# 780-00055_rev2_Pg1_SCH_NRES_Temp_Meas_8-.net
KiCad netlist of a schematic drawn in Altium Designer
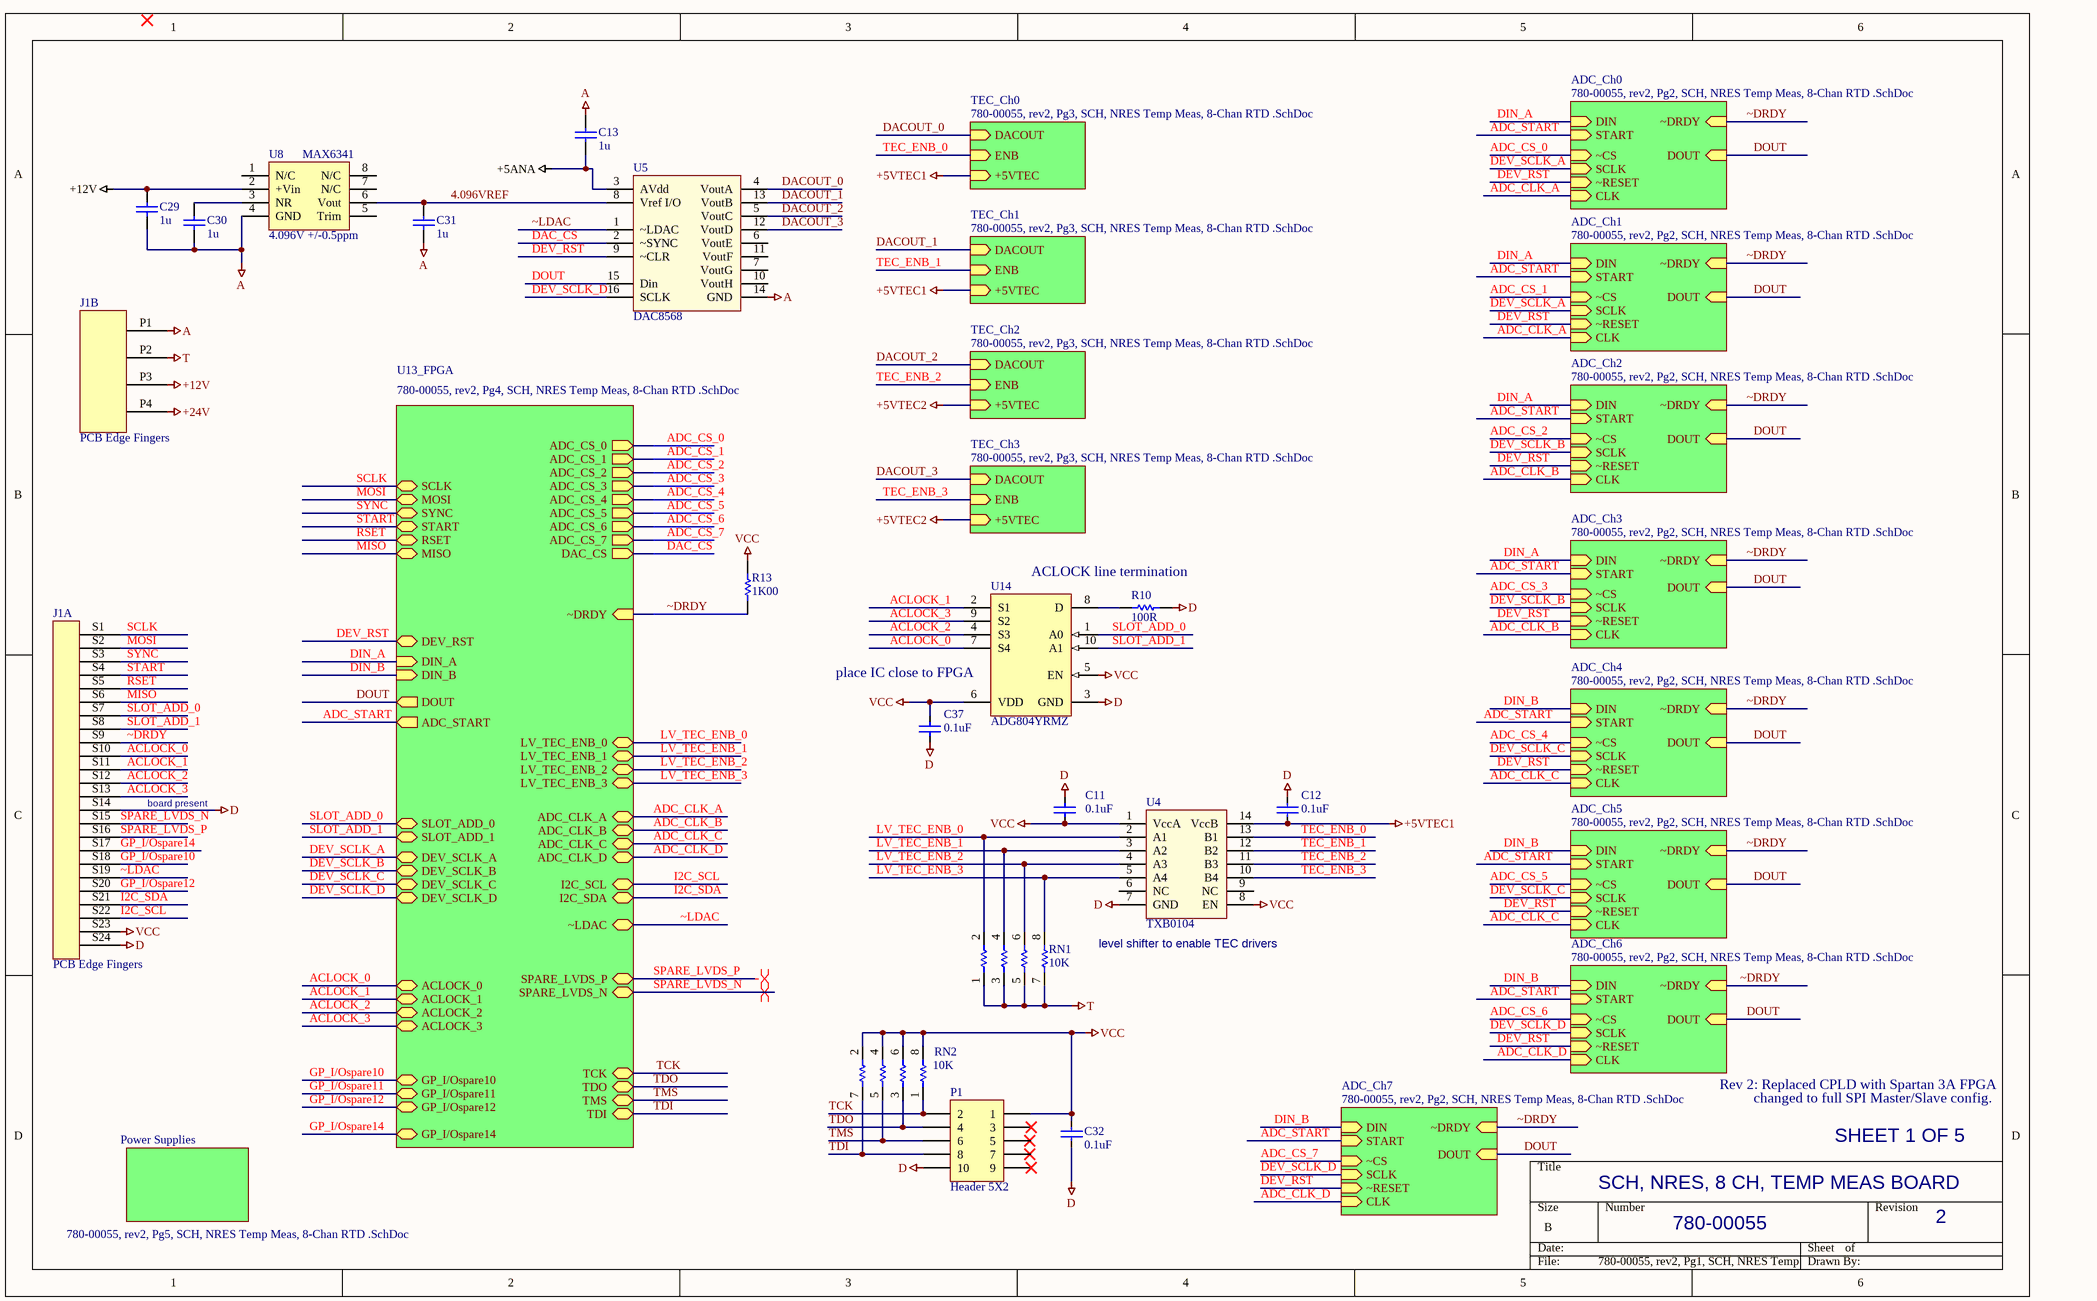
[diagram p0: 780-00055, rev2, Pg1, SCH, NRES Temp Meas, 8-Chan RTD .SchDoc]

(export (version "E")
  (design (tool "Eeschema 10.0.6"))
  (components
    (comp (ref "C11")
      (value "0.1uF")
      (footprint "SMD_0805")
      (description "Capacitor")
      (fields (field (name "Comment") "Cap SMD"))
      (libsource (lib "Richs Schematic Components") (part "Cap SMD"))
    )
    (comp (ref "C12")
      (value "0.1uF")
      (footprint "SMD_0805")
      (description "Capacitor")
      (fields (field (name "Comment") "Cap SMD"))
      (libsource (lib "Richs Schematic Components") (part "Cap SMD"))
    )
    (comp (ref "C13")
      (value "1u")
      (footprint "SMD_0805")
      (description "Capacitor")
      (fields (field (name "MANUFACTURER") "Taiyo Yuden"))
      (libsource (lib "Miscellaneous Devices") (part "Cap"))
    )
    (comp (ref "C29")
      (value "1u")
      (footprint "SMD_0805")
      (description "Capacitor")
      (fields (field (name "MANUFACTURER") "Taiyo Yuden"))
      (libsource (lib "Miscellaneous Devices") (part "Cap"))
    )
    (comp (ref "C30")
      (value "1u")
      (footprint "SMD_0805")
      (description "Capacitor")
      (fields (field (name "MANUFACTURER") "Taiyo Yuden"))
      (libsource (lib "Miscellaneous Devices") (part "Cap"))
    )
    (comp (ref "C31")
      (value "1u")
      (footprint "SMD_0805")
      (description "Capacitor")
      (fields (field (name "MANUFACTURER") "Taiyo Yuden"))
      (libsource (lib "Miscellaneous Devices") (part "Cap"))
    )
    (comp (ref "C32")
      (value "0.1uF")
      (footprint "SMD_0805")
      (description "Capacitor")
      (fields (field (name "MANUFACTURER") "AVX") (field (name "Comment") "Cap SMD"))
      (libsource (lib "Richs Schematic Components") (part "Cap SMD"))
    )
    (comp (ref "C37")
      (value "0.1uF")
      (footprint "SMD_0805")
      (description "Capacitor")
      (fields (field (name "Comment") "Cap SMD"))
      (libsource (lib "Richs Schematic Components") (part "Cap SMD"))
    )
    (comp (ref "J1")
      (value "PCB Edge Fingers")
      (footprint "PCB EDGE, MOLEX 46114")
      (description "PCB Edge Conn to fit Molex 46114 backplane connector")
      (libsource (lib "Richs Schematic Components") (part "Conn, PCB Card Edge / Molex 46114, 24 sig / 4 pwr"))
    )
    (comp (ref "P1")
      (value "Header 5X2")
      (footprint "HDR 2x5 RT, SAMTEC TSW")
      (description "Header, 5-Pin, Dual row")
      (fields (field (name "MANUFACTURER") "FCI"))
      (libsource (lib "Miscellaneous Connectors") (part "Header 5X2"))
    )
    (comp (ref "R10")
      (value "100R")
      (footprint "SMD_0805")
      (description "Resistor 0805")
      (fields (field (name "MANUFACTURER") "Vishay/Dale") (field (name "Comment") "Res 0805"))
      (libsource (lib "Richs Schematic Components") (part "Res SMD"))
    )
    (comp (ref "R13")
      (value "1K00")
      (footprint "SMD_0805")
      (description "Resistor 0805")
      (fields (field (name "MANUFACTURER") "Vishay/Dale") (field (name "Comment") "Res 0805"))
      (libsource (lib "Richs Schematic Components") (part "Res SMD"))
    )
    (comp (ref "RN1")
      (value "10K")
      (footprint "RES ARRAY 0603 x 4")
      (description "Resistor Array 4 Isolated")
      (fields (field (name "MANUFACTURER") "PANASONIC - ECG") (field (name "Comment") "RES ARRAY  x4 10K"))
      (libsource (lib "Richs Schematic Components") (part "RES ARRAY  x4 10K"))
    )
    (comp (ref "RN2")
      (value "10K")
      (footprint "RES ARRAY 0603 x 4")
      (description "Resistor Array 4 Isolated")
      (fields (field (name "MANUFACTURER") "Panasonic ECG") (field (name "Comment") "RES ARRAY  x4"))
      (libsource (lib "Richs Schematic Components") (part "RES ARRAY  x4"))
    )
    (comp (ref "U4")
      (value "TXB0104")
      (footprint "TSSOP14")
      (description "4-Chan Logic Level Shifter Bi-directional")
      (fields (field (name "MANUFACTURER") "TI"))
      (libsource (lib "Richs Schematic Components") (part "TXB0104"))
    )
    (comp (ref "U5")
      (value "DAC8568")
      (footprint "TSSOP16")
      (description "8 Chan, 16-bit DAC, SPI Interface")
      (fields (field (name "MANUFACTURER") "TI"))
      (libsource (lib "Richs Schematic Components") (part "DAC8568"))
    )
    (comp (ref "U8")
      (value "4.096V +/-0.5ppm")
      (footprint "SO-8_M")
      (description "VREF 4.096V 0.5ppm")
      (fields (field (name "MANUFACTURER") "MAXIM") (field (name "ALTIUM_VALUE") "MAX6341"))
      (libsource (lib "Richs Schematic Components") (part "MAX6341"))
    )
    (comp (ref "U14")
      (value "ADG804YRMZ")
      (footprint "ADI-RM-10_L")
      (description "1.65 to 3.6 V, CMOS, 0.5 Ohm, 4-Channel Multiplexer, -40 to 125 degC, 10-pin SOP (RM-10), Tube")
      (fields (field (name "MANUFACTURER") "Analog Devices"))
      (libsource (lib "Altium Content Vault") (part "CMP-0798-00106-1"))
    )
  )
  (nets
    (net (code "1") (name "+5ANA") (class "Default")
      (node (ref "C13") (pin "2") (pinfunction "2_2") (pintype "passive"))
      (node (ref "U5") (pin "3") (pinfunction "AVdd_3") (pintype "passive"))
    )
    (net (code "2") (name "+5VTEC1") (class "Default")
      (node (ref "C12") (pin "1") (pinfunction "1_1") (pintype "passive"))
      (node (ref "U4") (pin "14") (pinfunction "VccB_14") (pintype "passive"))
    )
    (net (code "4") (name "+12V") (class "Default")
      (node (ref "C29") (pin "1") (pinfunction "1_1") (pintype "passive"))
      (node (ref "J1") (pin "P3") (pinfunction "S27_P3") (pintype "passive"))
      (node (ref "U8") (pin "2") (pinfunction "+Vin_2") (pintype "passive"))
    )
    (net (code "5") (name "+24V") (class "Default")
      (node (ref "J1") (pin "P4") (pinfunction "S28_P4") (pintype "passive"))
    )
    (net (code "6") (name "/4.096VREF") (class "Default")
      (node (ref "C31") (pin "1") (pinfunction "1_1") (pintype "passive"))
      (node (ref "U5") (pin "8") (pinfunction "Vref_I/O_8") (pintype "passive"))
      (node (ref "U8") (pin "6") (pinfunction "Vout_6") (pintype "passive"))
    )
    (net (code "7") (name "/ACLOCK_0") (class "Default")
      (node (ref "J1") (pin "S10") (pintype "passive"))
      (node (ref "U14") (pin "7") (pinfunction "S4_7") (pintype "passive"))
    )
    (net (code "8") (name "/ACLOCK_1") (class "Default")
      (node (ref "J1") (pin "S11") (pintype "passive"))
      (node (ref "U14") (pin "2") (pinfunction "S1_2") (pintype "passive"))
    )
    (net (code "9") (name "/ACLOCK_2") (class "Default")
      (node (ref "J1") (pin "S12") (pintype "passive"))
      (node (ref "U14") (pin "4") (pinfunction "S3_4") (pintype "passive"))
    )
    (net (code "10") (name "/ACLOCK_3") (class "Default")
      (node (ref "J1") (pin "S13") (pintype "passive"))
      (node (ref "U14") (pin "9") (pinfunction "S2_9") (pintype "passive"))
    )
    (net (code "24") (name "/DACOUT_0") (class "Default")
      (node (ref "U5") (pin "4") (pinfunction "VoutA_4") (pintype "passive"))
    )
    (net (code "25") (name "/DACOUT_1") (class "Default")
      (node (ref "U5") (pin "13") (pinfunction "VoutB_13") (pintype "passive"))
    )
    (net (code "26") (name "/DACOUT_2") (class "Default")
      (node (ref "U5") (pin "5") (pinfunction "VoutC_5") (pintype "passive"))
    )
    (net (code "27") (name "/DACOUT_3") (class "Default")
      (node (ref "U5") (pin "12") (pinfunction "VoutD_12") (pintype "passive"))
    )
    (net (code "28") (name "/DAC_CS") (class "Default")
      (node (ref "U5") (pin "2") (pinfunction "~SYNC_2") (pintype "passive"))
    )
    (net (code "29") (name "/DEV_RST") (class "Default")
      (node (ref "U5") (pin "9") (pinfunction "~CLR_9") (pintype "passive"))
    )
    (net (code "33") (name "/DEV_SCLK_D") (class "Default")
      (node (ref "U5") (pin "16") (pinfunction "SCLK_16") (pintype "passive"))
    )
    (net (code "36") (name "/DOUT") (class "Default")
      (node (ref "U5") (pin "15") (pinfunction "Din_15") (pintype "passive"))
    )
    (net (code "37") (name "/GP_I{slash}Ospare10") (class "Default")
      (node (ref "J1") (pin "S18") (pintype "passive"))
    )
    (net (code "39") (name "/GP_I{slash}Ospare12") (class "Default")
      (node (ref "J1") (pin "S20") (pintype "passive"))
    )
    (net (code "40") (name "/GP_I{slash}Ospare14") (class "Default")
      (node (ref "J1") (pin "S17") (pintype "passive"))
    )
    (net (code "41") (name "/I2C_SCL") (class "Default") (node (ref "J1") (pin "S22") (pintype "passive")))
    (net (code "42") (name "/I2C_SDA") (class "Default") (node (ref "J1") (pin "S21") (pintype "passive")))
    (net (code "43") (name "/LV_TEC_ENB_0") (class "Default")
      (node (ref "RN1") (pin "2") (pinfunction "2_2") (pintype "passive"))
      (node (ref "U4") (pin "2") (pinfunction "A1_2") (pintype "passive"))
    )
    (net (code "44") (name "/LV_TEC_ENB_1") (class "Default")
      (node (ref "RN1") (pin "4") (pinfunction "4_4") (pintype "passive"))
      (node (ref "U4") (pin "3") (pinfunction "A2_3") (pintype "passive"))
    )
    (net (code "45") (name "/LV_TEC_ENB_2") (class "Default")
      (node (ref "RN1") (pin "6") (pinfunction "6_6") (pintype "passive"))
      (node (ref "U4") (pin "4") (pinfunction "A3_4") (pintype "passive"))
    )
    (net (code "46") (name "/LV_TEC_ENB_3") (class "Default")
      (node (ref "RN1") (pin "8") (pinfunction "8_8") (pintype "passive"))
      (node (ref "U4") (pin "5") (pinfunction "A4_5") (pintype "passive"))
    )
    (net (code "47") (name "/MISO") (class "Default") (node (ref "J1") (pin "S6") (pintype "passive")))
    (net (code "48") (name "/MOSI") (class "Default") (node (ref "J1") (pin "S2") (pintype "passive")))
    (net (code "49") (name "/RSET") (class "Default") (node (ref "J1") (pin "S5") (pintype "passive")))
    (net (code "50") (name "/SCLK") (class "Default") (node (ref "J1") (pin "S1") (pintype "passive")))
    (net (code "51") (name "/SLOT_ADD_0") (class "Default")
      (node (ref "J1") (pin "S7") (pintype "passive"))
      (node (ref "U14") (pin "1") (pinfunction "A0_1") (pintype "input"))
    )
    (net (code "52") (name "/SLOT_ADD_1") (class "Default")
      (node (ref "J1") (pin "S8") (pintype "passive"))
      (node (ref "U14") (pin "10") (pinfunction "A1_10") (pintype "input"))
    )
    (net (code "53") (name "/SPARE_LVDS_N") (class "Default")
      (node (ref "J1") (pin "S15") (pintype "passive"))
    )
    (net (code "54") (name "/SPARE_LVDS_P") (class "Default")
      (node (ref "J1") (pin "S16") (pintype "passive"))
    )
    (net (code "55") (name "/START") (class "Default") (node (ref "J1") (pin "S4") (pintype "passive")))
    (net (code "56") (name "/SYNC") (class "Default") (node (ref "J1") (pin "S3") (pintype "passive")))
    (net (code "57") (name "/TCK") (class "Default")
      (node (ref "P1") (pin "2") (pinfunction "2_2") (pintype "passive"))
      (node (ref "RN2") (pin "1") (pinfunction "1_1") (pintype "passive"))
    )
    (net (code "58") (name "/TDI") (class "Default")
      (node (ref "P1") (pin "8") (pinfunction "8_8") (pintype "passive"))
      (node (ref "RN2") (pin "7") (pinfunction "1_7") (pintype "passive"))
    )
    (net (code "59") (name "/TDO") (class "Default")
      (node (ref "P1") (pin "4") (pinfunction "4_4") (pintype "passive"))
      (node (ref "RN2") (pin "3") (pinfunction "3_3") (pintype "passive"))
    )
    (net (code "60") (name "/TEC_ENB_0") (class "Default")
      (node (ref "U4") (pin "13") (pinfunction "B1_13") (pintype "passive"))
    )
    (net (code "61") (name "/TEC_ENB_1") (class "Default")
      (node (ref "U4") (pin "12") (pinfunction "B2_12") (pintype "passive"))
    )
    (net (code "62") (name "/TEC_ENB_2") (class "Default")
      (node (ref "U4") (pin "11") (pinfunction "B3_11") (pintype "passive"))
    )
    (net (code "63") (name "/TEC_ENB_3") (class "Default")
      (node (ref "U4") (pin "10") (pinfunction "B4_10") (pintype "passive"))
    )
    (net (code "64") (name "/TMS") (class "Default")
      (node (ref "P1") (pin "6") (pinfunction "6_6") (pintype "passive"))
      (node (ref "RN2") (pin "5") (pinfunction "5_5") (pintype "passive"))
    )
    (net (code "65") (name "/~DRDY") (class "Default")
      (node (ref "J1") (pin "S9") (pintype "passive"))
      (node (ref "R13") (pin "1") (pinfunction "1_1") (pintype "passive"))
    )
    (net (code "66") (name "/~LDAC") (class "Default")
      (node (ref "J1") (pin "S19") (pintype "passive"))
      (node (ref "U5") (pin "1") (pinfunction "~LDAC_1") (pintype "passive"))
    )
    (net (code "67") (name "A") (class "Default")
      (node (ref "C13") (pin "1") (pinfunction "1_1") (pintype "passive"))
      (node (ref "C29") (pin "2") (pinfunction "2_2") (pintype "passive"))
      (node (ref "C30") (pin "2") (pinfunction "2_2") (pintype "passive"))
      (node (ref "C31") (pin "2") (pinfunction "2_2") (pintype "passive"))
      (node (ref "J1") (pin "P1") (pinfunction "S25_P1") (pintype "passive"))
      (node (ref "U5") (pin "14") (pinfunction "GND_14") (pintype "passive"))
      (node (ref "U8") (pin "4") (pinfunction "GND_4") (pintype "passive"))
    )
    (net (code "68") (name "D") (class "Default")
      (node (ref "C11") (pin "2") (pinfunction "2_2") (pintype "passive"))
      (node (ref "C12") (pin "2") (pinfunction "2_2") (pintype "passive"))
      (node (ref "C32") (pin "1") (pinfunction "1_1") (pintype "passive"))
      (node (ref "C37") (pin "1") (pinfunction "1_1") (pintype "passive"))
      (node (ref "J1") (pin "S14") (pintype "passive"))
      (node (ref "J1") (pin "S24") (pintype "passive"))
      (node (ref "P1") (pin "10") (pinfunction "10_10") (pintype "passive"))
      (node (ref "R10") (pin "2") (pinfunction "2_2") (pintype "passive"))
      (node (ref "U14") (pin "3") (pinfunction "GND_3") (pintype "power_in"))
      (node (ref "U4") (pin "7") (pinfunction "GND_7") (pintype "passive"))
    )
    (net (code "69") (name "Net-(U8-NR)") (class "Default")
      (node (ref "C30") (pin "1") (pinfunction "1_1") (pintype "passive"))
      (node (ref "U8") (pin "3") (pinfunction "NR_3") (pintype "passive"))
    )
    (net (code "70") (name "Net-(U14-D)") (class "Default")
      (node (ref "R10") (pin "1") (pinfunction "1_1") (pintype "passive"))
      (node (ref "U14") (pin "8") (pinfunction "D_8") (pintype "passive"))
    )
    (net (code "71") (name "T") (class "Default")
      (node (ref "J1") (pin "P2") (pinfunction "S26_P2") (pintype "passive"))
      (node (ref "RN1") (pin "1") (pinfunction "1_1") (pintype "passive"))
      (node (ref "RN1") (pin "3") (pinfunction "3_3") (pintype "passive"))
      (node (ref "RN1") (pin "5") (pinfunction "5_5") (pintype "passive"))
      (node (ref "RN1") (pin "7") (pinfunction "1_7") (pintype "passive"))
    )
    (net (code "72") (name "VCC") (class "Default")
      (node (ref "C11") (pin "1") (pinfunction "1_1") (pintype "passive"))
      (node (ref "C32") (pin "2") (pinfunction "2_2") (pintype "passive"))
      (node (ref "C37") (pin "2") (pinfunction "2_2") (pintype "passive"))
      (node (ref "J1") (pin "S23") (pintype "passive"))
      (node (ref "P1") (pin "1") (pinfunction "1_1") (pintype "passive"))
      (node (ref "R13") (pin "2") (pinfunction "2_2") (pintype "passive"))
      (node (ref "RN2") (pin "2") (pinfunction "2_2") (pintype "passive"))
      (node (ref "RN2") (pin "4") (pinfunction "4_4") (pintype "passive"))
      (node (ref "RN2") (pin "6") (pinfunction "6_6") (pintype "passive"))
      (node (ref "RN2") (pin "8") (pinfunction "8_8") (pintype "passive"))
      (node (ref "U14") (pin "5") (pinfunction "EN_5") (pintype "input"))
      (node (ref "U14") (pin "6") (pinfunction "VDD_6") (pintype "power_in"))
      (node (ref "U4") (pin "1") (pinfunction "VccA_1") (pintype "passive"))
      (node (ref "U4") (pin "8") (pinfunction "EN_8") (pintype "passive"))
    )
    (net (code "73") (name "unconnected-(P1-Pad3)") (class "Default")
      (node (ref "P1") (pin "3") (pinfunction "3_3") (pintype "passive+no_connect"))
    )
    (net (code "74") (name "unconnected-(P1-Pad5)") (class "Default")
      (node (ref "P1") (pin "5") (pinfunction "5_5") (pintype "passive"))
    )
    (net (code "75") (name "unconnected-(P1-Pad7)") (class "Default")
      (node (ref "P1") (pin "7") (pinfunction "7_7") (pintype "passive"))
    )
    (net (code "76") (name "unconnected-(P1-Pad9)") (class "Default")
      (node (ref "P1") (pin "9") (pinfunction "9_9") (pintype "passive+no_connect"))
    )
    (net (code "77") (name "unconnected-(U4-NC-Pad6)") (class "Default")
      (node (ref "U4") (pin "6") (pinfunction "NC_6") (pintype "passive"))
    )
    (net (code "78") (name "unconnected-(U4-NC-Pad9)") (class "Default")
      (node (ref "U4") (pin "9") (pinfunction "NC_9") (pintype "passive"))
    )
    (net (code "79") (name "unconnected-(U5-VoutE-Pad6)") (class "Default")
      (node (ref "U5") (pin "6") (pinfunction "VoutE_6") (pintype "passive"))
    )
    (net (code "80") (name "unconnected-(U5-VoutF-Pad11)") (class "Default")
      (node (ref "U5") (pin "11") (pinfunction "VoutF_11") (pintype "passive"))
    )
    (net (code "81") (name "unconnected-(U5-VoutG-Pad7)") (class "Default")
      (node (ref "U5") (pin "7") (pinfunction "VoutG_7") (pintype "passive"))
    )
    (net (code "82") (name "unconnected-(U5-VoutH-Pad10)") (class "Default")
      (node (ref "U5") (pin "10") (pinfunction "VoutH_10") (pintype "passive"))
    )
    (net (code "83") (name "unconnected-(U8-N{slash}C-Pad1)") (class "Default")
      (node (ref "U8") (pin "1") (pinfunction "N/C_1") (pintype "passive"))
    )
    (net (code "84") (name "unconnected-(U8-N{slash}C-Pad7)") (class "Default")
      (node (ref "U8") (pin "7") (pinfunction "N/C_7") (pintype "passive"))
    )
    (net (code "85") (name "unconnected-(U8-N{slash}C-Pad8)") (class "Default")
      (node (ref "U8") (pin "8") (pinfunction "N/C_8") (pintype "passive"))
    )
    (net (code "86") (name "unconnected-(U8-Trim-Pad5)") (class "Default")
      (node (ref "U8") (pin "5") (pinfunction "Trim_5") (pintype "passive"))
    )
  )
)
